# HIenthi.net
KiCad netlist of a schematic drawn in Altium Designer
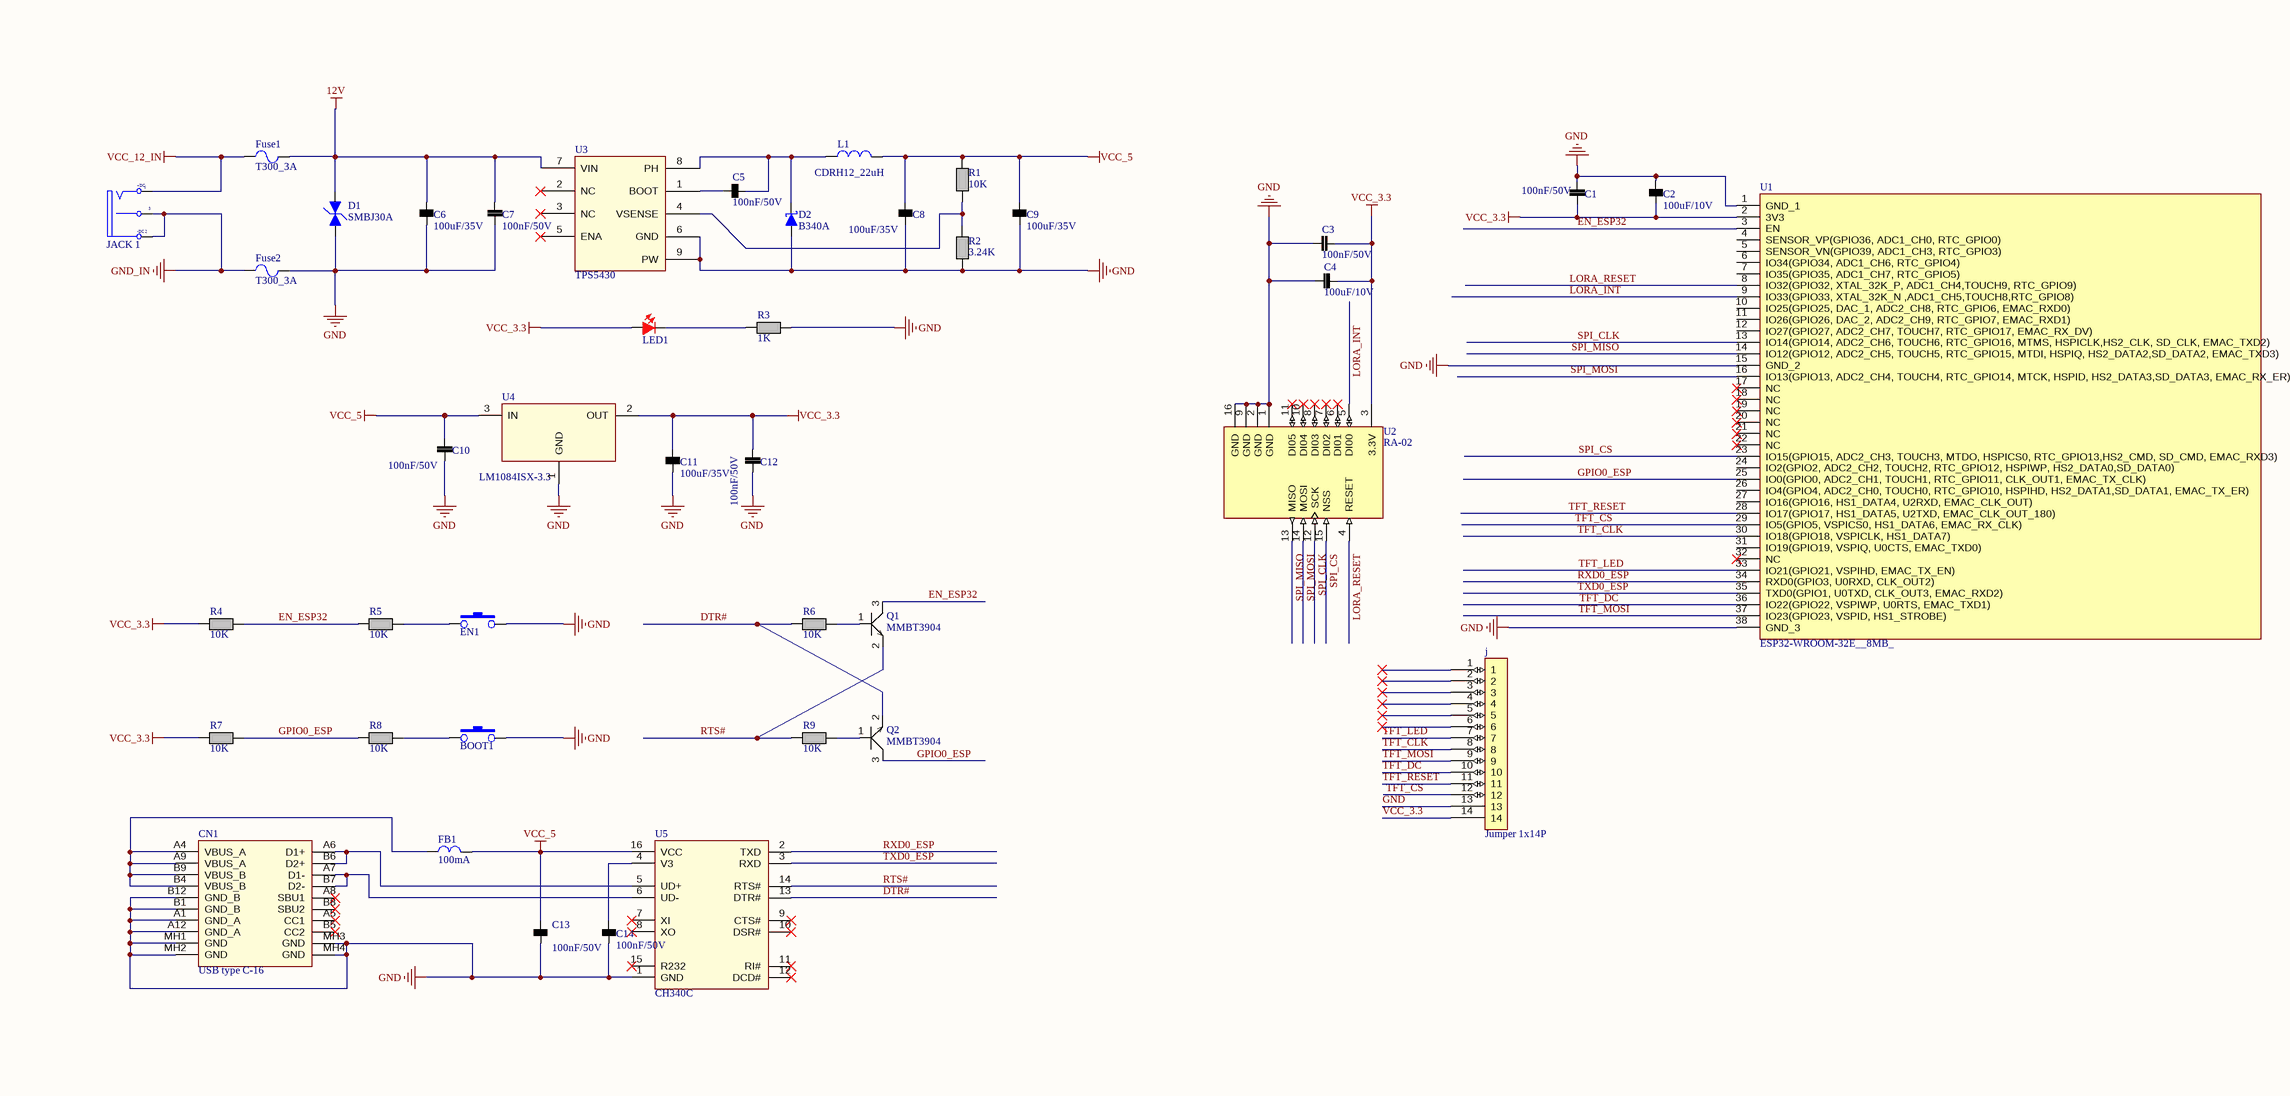
[diagram p0: HIenthi.SchDoc]

(export (version "E")
  (design (tool "Eeschema 10.0.6"))
  (components
    (comp (ref "BOOT1")
      (value "SW_2pin_SMD")
      (footprint "SW2-SMD**")
      (libsource (lib "Milky_Way") (part "SW_2pin_SMD"))
    )
    (comp (ref "C1")
      (value "100nF/50V")
      (footprint "CAP-0805**")
      (description "2Pin-SMD-0805 ,Ceramic X7R")
      (libsource (lib "Milky_Way") (part "Cap-100nF/50V_0805"))
    )
    (comp (ref "C2")
      (value "100uF/10V")
      (footprint "CAP_TANTA_SMD3528")
      (description "Cap-Tantalum  SMD3528 3.5mm x 2.8mm")
      (libsource (lib "") (part "Cap-Tanta_100uF/10V 3528_1"))
    )
    (comp (ref "C3")
      (value "100nF/50V")
      (footprint "CAP-0805**")
      (description "2Pin-SMD-0805 ,Ceramic X7R")
      (libsource (lib "Milky_Way") (part "Cap-100nF/50V_0805"))
    )
    (comp (ref "C4")
      (value "100uF/10V")
      (footprint "CAP_TANTA_SMD3528")
      (description "Cap-Tantalum  SMD3528 3.5mm x 2.8mm")
      (libsource (lib "Milky_Way") (part "Cap-Tanta_100uF/10V 3528"))
    )
    (comp (ref "C5")
      (value "100nF/50V")
      (footprint "CAP-0805**")
      (description "2Pin-SMD-0805 ,Ceramic X7R")
      (libsource (lib "Milky_Way") (part "Cap-100nF/50V_0805"))
    )
    (comp (ref "C6")
      (value "100uF/35V")
      (footprint "CAP-AL- Size D8_6.3×7.7 mm**")
      (description "Cap-Al-Size D8_6.3×7.7 mm")
      (libsource (lib "Milky_Way") (part "Cap-Al_100uF/35V"))
    )
    (comp (ref "C7")
      (value "100nF/50V")
      (footprint "CAP-0805**")
      (description "2Pin-SMD-0805 ,Ceramic X7R")
      (libsource (lib "Milky_Way") (part "Cap-100nF/50V_0805"))
    )
    (comp (ref "C8")
      (value "100uF/35V")
      (footprint "CAP-AL- Size D8_6.3×7.7 mm**")
      (description "Cap-Al-Size D8_6.3×7.7 mm")
      (libsource (lib "Milky_Way") (part "Cap-Al_100uF/35V"))
    )
    (comp (ref "C9")
      (value "100uF/35V")
      (footprint "CAP-AL- Size D8_6.3×7.7 mm**")
      (description "Cap-Al-Size D8_6.3×7.7 mm")
      (libsource (lib "Milky_Way") (part "Cap-Al_100uF/35V"))
    )
    (comp (ref "C10")
      (value "100nF/50V")
      (footprint "CAP-0805**")
      (description "2Pin-SMD-0805 ,Ceramic X7R")
      (libsource (lib "Milky_Way") (part "Cap-100nF/50V_0805"))
    )
    (comp (ref "C11")
      (value "100uF/35V")
      (footprint "CAP-AL- Size D8_6.3×7.7 mm**")
      (description "Cap-Al-Size D8_6.3×7.7 mm")
      (libsource (lib "Milky_Way") (part "Cap-Al_100uF/35V"))
    )
    (comp (ref "C12")
      (value "100nF/50V")
      (footprint "CAP-0805**")
      (description "2Pin-SMD-0805 ,Ceramic X7R")
      (libsource (lib "Milky_Way") (part "Cap-100nF/50V_0805"))
    )
    (comp (ref "C13")
      (value "100nF/50V")
      (footprint "CAP-0805**")
      (description "2Pin-SMD-0805 ,Ceramic X7R")
      (libsource (lib "Milky_Way") (part "Cap-100nF/50V_0805"))
    )
    (comp (ref "C14")
      (value "100nF/50V")
      (footprint "CAP-0805**")
      (description "2Pin-SMD-0805 ,Ceramic X7R")
      (libsource (lib "Milky_Way") (part "Cap-100nF/50V_0805"))
    )
    (comp (ref "CN1")
      (value "USB type C-16")
      (footprint "USB TYPE C-16**")
      (fields (field (name "MF") "Valcon") (field (name "MP") "CSP-USC16-TR"))
      (libsource (lib "Milky_Way") (part "USB type C-16"))
    )
    (comp (ref "D1")
      (value "SMBJ30A")
      (footprint "DO-214AA**")
      (description "DO-214AA**")
      (libsource (lib "Milky_Way") (part "D-TVS_SMBJ30A"))
    )
    (comp (ref "D2")
      (value "B340A")
      (footprint "DO-214AC**")
      (description "DO_214AC")
      (fields (field (name "PUBLISHER") "Altium Limited"))
      (libsource (lib "Milky_Way") (part "DSchottky_B340A"))
    )
    (comp (ref "EN1")
      (value "SW_2pin_SMD")
      (footprint "SW2-SMD**")
      (libsource (lib "Milky_Way") (part "SW_2pin_SMD"))
    )
    (comp (ref "FB1")
      (value "100mA")
      (footprint "FB 0805**")
      (description "FB0805/600R/0805")
      (fields (field (name "PUBLISHER") "Altium Limited"))
      (libsource (lib "Milky_Way") (part "FB0805/600R_0805"))
    )
    (comp (ref "Fuse1")
      (value "T300_3A")
      (footprint "FUSE-1812**")
      (description "SMD 1812")
      (libsource (lib "Milky_Way") (part "FUSE 3A _1812"))
    )
    (comp (ref "Fuse2")
      (value "T300_3A")
      (footprint "FUSE-1812**")
      (description "SMD 1812")
      (libsource (lib "Milky_Way") (part "FUSE 3A _1812"))
    )
    (comp (ref "j")
      (value "Jumper 1x14P")
      (footprint "IOT_v1:JUMP1x14")
      (libsource (lib "Schlib1") (part "Jumper 1x14P"))
    )
    (comp (ref "JACK 1")
      (value "DC3501")
      (footprint "DC_005**")
      (description "Jack DC3.5x1.3MM DC3501")
      (libsource (lib "IOT_v1_1") (part "Jack  DC3501"))
    )
    (comp (ref "L1")
      (value "CDRH12_22uH")
      (footprint "IND_CDRH12_12x12x7MM**")
      (description "CDRH12_12x12x7MM**")
      (fields
        (field (name "MANUFACTURER") "Generic Components")
        (field (name "PUBLISHER") "Altium Hobart Technology Centre")
      )
      (libsource (lib "Milky_Way") (part "IN_CDRH12_22uH"))
    )
    (comp (ref "LED1")
      (value "LedRed")
      (footprint "LED-0805-Red**")
      (description "2Pin-SMD")
      (libsource (lib "Milky_Way") (part "LedRed"))
    )
    (comp (ref "Q1")
      (value "MMBT3904")
      (footprint "SOT23-3 **")
      (description "3PIN-SOT23,MMBT3904")
      (libsource (lib "Milky_Way") (part "TRA-N_MMBT3904"))
    )
    (comp (ref "Q2")
      (value "MMBT3904")
      (footprint "SOT23-3 **")
      (description "3PIN-SOT23,MMBT3904")
      (libsource (lib "Milky_Way") (part "TRA-N_MMBT3904"))
    )
    (comp (ref "R1")
      (value "10K")
      (footprint "Res-0805**")
      (description "Res-10K 0805 SMD")
      (libsource (lib "Milky_Way") (part "Res-10K 0805 SMD"))
    )
    (comp (ref "R2")
      (value "3.24K")
      (footprint "Res-0805**")
      (description "Res-3.24K 0805 SMD")
      (libsource (lib "Milky_Way") (part "Res-3.24K 0805 SMD"))
    )
    (comp (ref "R3")
      (value "1K")
      (footprint "Res-0805**")
      (description "Res-1K 0805 SMD")
      (libsource (lib "Milky_Way") (part "Res-1K 0805 SMD"))
    )
    (comp (ref "R4")
      (value "10K")
      (footprint "Res-0805**")
      (description "Res-10K 0805 SMD")
      (libsource (lib "Milky_Way") (part "Res-10K 0805 SMD"))
    )
    (comp (ref "R5")
      (value "10K")
      (footprint "Res-0805**")
      (description "Res-10K 0805 SMD")
      (libsource (lib "Milky_Way") (part "Res-10K 0805 SMD"))
    )
    (comp (ref "R6")
      (value "10K")
      (footprint "Res-0805**")
      (description "Res-10K 0805 SMD")
      (libsource (lib "Milky_Way") (part "Res-10K 0805 SMD"))
    )
    (comp (ref "R7")
      (value "10K")
      (footprint "Res-0805**")
      (description "Res-10K 0805 SMD")
      (libsource (lib "Milky_Way") (part "Res-10K 0805 SMD"))
    )
    (comp (ref "R8")
      (value "10K")
      (footprint "Res-0805**")
      (description "Res-10K 0805 SMD")
      (libsource (lib "Milky_Way") (part "Res-10K 0805 SMD"))
    )
    (comp (ref "R9")
      (value "10K")
      (footprint "Res-0805**")
      (description "Res-10K 0805 SMD")
      (libsource (lib "Milky_Way") (part "Res-10K 0805 SMD"))
    )
    (comp (ref "U1")
      (value "ESP32-WROOM-32E__8MB_")
      (footprint "ESP32WROOM32E8MB")
      (description "Integrated Circuit")
      (fields
        (field (name "MANUFACTURER_PART_NUMBER") "ESP32-WROOM-32E (8MB)")
        (field (name "MOUSER PART NUMBER") "356-ESP32WRM32E164PH")
      )
      (libsource (lib "IOT_v1_1") (part "ESP32-WROOM-32E__8MB_"))
    )
    (comp (ref "U2")
      (value "RA-02")
      (footprint "RA-02")
      (fields (field (name "MF") "Ai-Thinker"))
      (libsource (lib "RA-02") (part "RA-02"))
    )
    (comp (ref "U3")
      (value "TPS5430")
      (footprint "SOIC8-PAD**")
      (description "SOIC8 pad-Height 1.7mm")
      (libsource (lib "Milky_Way") (part "TPS5430"))
    )
    (comp (ref "U4")
      (value "LM1084ISX-3.3")
      (footprint "TO-263/D2PAK")
      (description "TO263-3")
      (libsource (lib "Milky_Way") (part "LM1084ISX-3.3"))
    )
    (comp (ref "U5")
      (value "CH340C")
      (footprint "SOIC-16**")
      (description "16Pin-SOIC")
      (libsource (lib "Milky_Way") (part "CH340C"))
    )
  )
  (nets
    (net (code "1") (name "/DTR#") (class "Default")
      (node (ref "Q2") (pin "2") (pinfunction "2_2") (pintype "passive"))
      (node (ref "R6") (pin "2") (pinfunction "2_2") (pintype "passive"))
      (node (ref "U5") (pin "13") (pinfunction "DTR#_13") (pintype "passive"))
    )
    (net (code "2") (name "/EN_ESP32") (class "Default")
      (node (ref "Q1") (pin "3") (pinfunction "3_3") (pintype "passive"))
      (node (ref "R4") (pin "1") (pinfunction "1_1") (pintype "passive"))
      (node (ref "R5") (pin "2") (pinfunction "2_2") (pintype "passive"))
      (node (ref "U1") (pin "3") (pinfunction "EN_3") (pintype "passive"))
    )
    (net (code "3") (name "/GPIO0_ESP") (class "Default")
      (node (ref "Q2") (pin "3") (pinfunction "3_3") (pintype "passive"))
      (node (ref "R7") (pin "1") (pinfunction "1_1") (pintype "passive"))
      (node (ref "R8") (pin "2") (pinfunction "2_2") (pintype "passive"))
      (node (ref "U1") (pin "25") (pinfunction "IO0(GPIO0,_ADC2_CH1,_TOUCH1,_RTC_GPIO11,_CLK_OUT1,_EMAC_TX_CLK)_25") (pintype "passive"))
    )
    (net (code "4") (name "/LORA_INT") (class "Default")
      (node (ref "U1") (pin "9") (pinfunction "IO33(GPIO33,_XTAL_32K_N_,ADC1_CH5,TOUCH8,RTC_GPIO8)_9") (pintype "passive"))
      (node (ref "U2") (pin "5") (pinfunction "DI00_5") (pintype "bidirectional"))
    )
    (net (code "5") (name "/LORA_RESET") (class "Default")
      (node (ref "U1") (pin "8") (pinfunction "IO32(GPIO32,_XTAL_32K_P,_ADC1_CH4,TOUCH9,_RTC_GPIO9)_8") (pintype "passive"))
      (node (ref "U2") (pin "4") (pinfunction "RESET_4") (pintype "input"))
    )
    (net (code "6") (name "/RTS#") (class "Default")
      (node (ref "Q1") (pin "2") (pinfunction "2_2") (pintype "passive"))
      (node (ref "R9") (pin "2") (pinfunction "2_2") (pintype "passive"))
      (node (ref "U5") (pin "14") (pinfunction "RTS#_14") (pintype "passive"))
    )
    (net (code "7") (name "/RXD0_ESP") (class "Default")
      (node (ref "U1") (pin "34") (pinfunction "RXD0(GPIO3,_U0RXD,_CLK_OUT2)_34") (pintype "passive"))
      (node (ref "U5") (pin "2") (pinfunction "TXD_2") (pintype "passive"))
    )
    (net (code "8") (name "/SPI_CLK") (class "Default")
      (node (ref "U1") (pin "13") (pinfunction "IO14(GPIO14,_ADC2_CH6,_TOUCH6,_RTC_GPIO16,_MTMS,_HSPICLK,HS2_CLK,_SD_CLK,_EMAC_TXD2)_13") (pintype "passive"))
      (node (ref "U2") (pin "12") (pinfunction "SCK_12") (pintype "input"))
    )
    (net (code "9") (name "/SPI_CS") (class "Default")
      (node (ref "U1") (pin "23") (pinfunction "IO15(GPIO15,_ADC2_CH3,_TOUCH3,_MTDO,_HSPICS0,_RTC_GPIO13,HS2_CMD,_SD_CMD,_EMAC_RXD3)_23") (pintype "passive"))
      (node (ref "U2") (pin "15") (pinfunction "NSS_15") (pintype "input"))
    )
    (net (code "10") (name "/SPI_MISO") (class "Default")
      (node (ref "U1") (pin "14") (pinfunction "IO12(GPIO12,_ADC2_CH5,_TOUCH5,_RTC_GPIO15,_MTDI,_HSPIQ,_HS2_DATA2,SD_DATA2,_EMAC_TXD3)_14") (pintype "passive"))
      (node (ref "U2") (pin "13") (pinfunction "MISO_13") (pintype "output"))
    )
    (net (code "11") (name "/SPI_MOSI") (class "Default")
      (node (ref "U1") (pin "16") (pinfunction "IO13(GPIO13,_ADC2_CH4,_TOUCH4,_RTC_GPIO14,_MTCK,_HSPID,_HS2_DATA3,SD_DATA3,_EMAC_RX_ER)_16") (pintype "passive"))
      (node (ref "U2") (pin "14") (pinfunction "MOSI_14") (pintype "input"))
    )
    (net (code "12") (name "/TFT_CLK") (class "Default")
      (node (ref "U1") (pin "30") (pinfunction "IO18(GPIO18,_VSPICLK,_HS1_DATA7)_30") (pintype "passive"))
      (node (ref "j") (pin "8") (pinfunction "8_8") (pintype "bidirectional"))
    )
    (net (code "13") (name "/TFT_CS") (class "Default")
      (node (ref "U1") (pin "29") (pinfunction "IO5(GPIO5,_VSPICS0,_HS1_DATA6,_EMAC_RX_CLK)_29") (pintype "passive"))
      (node (ref "j") (pin "12") (pinfunction "12_12") (pintype "bidirectional"))
    )
    (net (code "14") (name "/TFT_DC") (class "Default")
      (node (ref "U1") (pin "36") (pinfunction "IO22(GPIO22,_VSPIWP,_U0RTS,_EMAC_TXD1)_36") (pintype "passive"))
      (node (ref "j") (pin "10") (pinfunction "10_10") (pintype "bidirectional"))
    )
    (net (code "15") (name "/TFT_LED") (class "Default")
      (node (ref "U1") (pin "33") (pinfunction "IO21(GPIO21,_VSPIHD,_EMAC_TX_EN)_33") (pintype "passive"))
      (node (ref "j") (pin "7") (pinfunction "7_7") (pintype "bidirectional"))
    )
    (net (code "16") (name "/TFT_MOSI") (class "Default")
      (node (ref "U1") (pin "37") (pinfunction "IO23(GPIO23,_VSPID,_HS1_STROBE)_37") (pintype "passive"))
      (node (ref "j") (pin "9") (pinfunction "9_9") (pintype "bidirectional"))
    )
    (net (code "17") (name "/TFT_RESET") (class "Default")
      (node (ref "U1") (pin "28") (pinfunction "IO17(GPIO17,_HS1_DATA5,_U2TXD,_EMAC_CLK_OUT_180)_28") (pintype "passive"))
      (node (ref "j") (pin "11") (pinfunction "11_11") (pintype "bidirectional"))
    )
    (net (code "18") (name "/TXD0_ESP") (class "Default")
      (node (ref "U1") (pin "35") (pinfunction "TXD0(GPIO1,_U0TXD,_CLK_OUT3,_EMAC_RXD2)_35") (pintype "passive"))
      (node (ref "U5") (pin "3") (pinfunction "RXD_3") (pintype "passive"))
    )
    (net (code "19") (name "12V") (class "Default")
      (node (ref "C6") (pin "1") (pinfunction "+_1") (pintype "passive"))
      (node (ref "C7") (pin "2") (pinfunction "2_2") (pintype "passive"))
      (node (ref "D1") (pin "2") (pinfunction "A_2") (pintype "passive"))
      (node (ref "Fuse1") (pin "2") (pinfunction "2_2") (pintype "passive"))
      (node (ref "U3") (pin "7") (pinfunction "VIN_7") (pintype "passive"))
    )
    (net (code "20") (name "GND") (class "Default")
      (node (ref "BOOT1") (pin "2") (pinfunction "2_2") (pintype "passive"))
      (node (ref "C1") (pin "2") (pinfunction "2_2") (pintype "passive"))
      (node (ref "C10") (pin "1") (pinfunction "1_1") (pintype "passive"))
      (node (ref "C11") (pin "2") (pinfunction "-_2") (pintype "passive"))
      (node (ref "C12") (pin "1") (pinfunction "1_1") (pintype "passive"))
      (node (ref "C13") (pin "2") (pinfunction "2_2") (pintype "passive"))
      (node (ref "C14") (pin "2") (pinfunction "2_2") (pintype "passive"))
      (node (ref "C2") (pin "2") (pinfunction "-_2") (pintype "passive"))
      (node (ref "C3") (pin "1") (pinfunction "1_1") (pintype "passive"))
      (node (ref "C4") (pin "2") (pinfunction "-_2") (pintype "passive"))
      (node (ref "C6") (pin "2") (pinfunction "-_2") (pintype "passive"))
      (node (ref "C7") (pin "1") (pinfunction "1_1") (pintype "passive"))
      (node (ref "C8") (pin "2") (pinfunction "-_2") (pintype "passive"))
      (node (ref "C9") (pin "2") (pinfunction "-_2") (pintype "passive"))
      (node (ref "CN1") (pin "A1") (pinfunction "GND_A_A1") (pintype "power_in"))
      (node (ref "CN1") (pin "A12") (pinfunction "GND_A_A12") (pintype "power_in"))
      (node (ref "CN1") (pin "B1") (pinfunction "GND_B_B1") (pintype "power_in"))
      (node (ref "CN1") (pin "B12") (pinfunction "GND_B_B12") (pintype "power_in"))
      (node (ref "CN1") (pin "MH1") (pinfunction "GND_MH1") (pintype "power_in"))
      (node (ref "CN1") (pin "MH2") (pinfunction "GND_MH2") (pintype "power_in"))
      (node (ref "CN1") (pin "MH3") (pinfunction "GND_MH3") (pintype "power_in"))
      (node (ref "CN1") (pin "MH4") (pinfunction "GND_MH4") (pintype "power_in"))
      (node (ref "D1") (pin "1") (pinfunction "A_1") (pintype "passive"))
      (node (ref "D2") (pin "1") (pinfunction "A_1") (pintype "passive"))
      (node (ref "EN1") (pin "2") (pinfunction "2_2") (pintype "passive"))
      (node (ref "Fuse2") (pin "2") (pinfunction "2_2") (pintype "passive"))
      (node (ref "R2") (pin "1") (pinfunction "1_1") (pintype "passive"))
      (node (ref "R3") (pin "1") (pinfunction "1_1") (pintype "passive"))
      (node (ref "U1") (pin "1") (pinfunction "GND_1_1") (pintype "passive"))
      (node (ref "U1") (pin "15") (pinfunction "GND_2_15") (pintype "passive"))
      (node (ref "U1") (pin "38") (pinfunction "GND_3_38") (pintype "passive"))
      (node (ref "U2") (pin "1") (pinfunction "GND_1") (pintype "power_in"))
      (node (ref "U2") (pin "16") (pinfunction "GND_16") (pintype "power_in"))
      (node (ref "U2") (pin "2") (pinfunction "GND_2") (pintype "power_in"))
      (node (ref "U2") (pin "9") (pinfunction "GND_9") (pintype "power_in"))
      (node (ref "U3") (pin "6") (pinfunction "GND_6") (pintype "passive"))
      (node (ref "U3") (pin "9") (pinfunction "PW_9") (pintype "passive"))
      (node (ref "U4") (pin "1") (pinfunction "GND_1") (pintype "passive"))
      (node (ref "U5") (pin "1") (pinfunction "GND_1") (pintype "passive"))
      (node (ref "j") (pin "13") (pinfunction "13_13") (pintype "power_in"))
    )
    (net (code "21") (name "GND_IN") (class "Default")
      (node (ref "Fuse2") (pin "1") (pinfunction "1_1") (pintype "passive"))
      (node (ref "JACK 1") (pin "2") (pinfunction "TN_2") (pintype "passive"))
      (node (ref "JACK 1") (pin "3") (pinfunction "S_3") (pintype "power_in"))
    )
    (net (code "22") (name "Net-(BOOT1-Pad1)") (class "Default")
      (node (ref "BOOT1") (pin "1") (pinfunction "1_1") (pintype "passive"))
      (node (ref "R8") (pin "1") (pinfunction "1_1") (pintype "passive"))
    )
    (net (code "23") (name "Net-(CN1-D1+)") (class "Default")
      (node (ref "CN1") (pin "A6") (pinfunction "D1+_A6") (pintype "passive"))
      (node (ref "CN1") (pin "B6") (pinfunction "D2+_B6") (pintype "passive"))
      (node (ref "U5") (pin "5") (pinfunction "UD+_5") (pintype "passive"))
    )
    (net (code "24") (name "Net-(CN1-D1-)") (class "Default")
      (node (ref "CN1") (pin "A7") (pinfunction "D1-_A7") (pintype "passive"))
      (node (ref "CN1") (pin "B7") (pinfunction "D2-_B7") (pintype "passive"))
      (node (ref "U5") (pin "6") (pinfunction "UD-_6") (pintype "passive"))
    )
    (net (code "25") (name "Net-(CN1-VBUS_A-PadA4)") (class "Default")
      (node (ref "CN1") (pin "A4") (pinfunction "VBUS_A_A4") (pintype "power_in"))
      (node (ref "CN1") (pin "A9") (pinfunction "VBUS_A_A9") (pintype "power_in"))
      (node (ref "CN1") (pin "B4") (pinfunction "VBUS_B_B4") (pintype "power_in"))
      (node (ref "CN1") (pin "B9") (pinfunction "VBUS_B_B9") (pintype "power_in"))
      (node (ref "FB1") (pin "1") (pinfunction "1_1") (pintype "passive"))
    )
    (net (code "26") (name "Net-(D2-K)") (class "Default")
      (node (ref "C5") (pin "2") (pinfunction "2_2") (pintype "passive"))
      (node (ref "D2") (pin "2") (pinfunction "K_2") (pintype "passive"))
      (node (ref "L1") (pin "1") (pinfunction "1_1") (pintype "passive"))
      (node (ref "U3") (pin "8") (pinfunction "PH_8") (pintype "passive"))
    )
    (net (code "27") (name "Net-(EN1-Pad1)") (class "Default")
      (node (ref "EN1") (pin "1") (pinfunction "1_1") (pintype "passive"))
      (node (ref "R5") (pin "1") (pinfunction "1_1") (pintype "passive"))
    )
    (net (code "28") (name "Net-(LED1-K)") (class "Default")
      (node (ref "LED1") (pin "2") (pinfunction "K_2") (pintype "passive"))
      (node (ref "R3") (pin "2") (pinfunction "2_2") (pintype "passive"))
    )
    (net (code "29") (name "Net-(Q1-Pad1)") (class "Default")
      (node (ref "Q1") (pin "1") (pinfunction "1_1") (pintype "passive"))
      (node (ref "R6") (pin "1") (pinfunction "1_1") (pintype "passive"))
    )
    (net (code "30") (name "Net-(Q2-Pad1)") (class "Default")
      (node (ref "Q2") (pin "1") (pinfunction "1_1") (pintype "passive"))
      (node (ref "R9") (pin "1") (pinfunction "1_1") (pintype "passive"))
    )
    (net (code "31") (name "Net-(U3-BOOT)") (class "Default")
      (node (ref "C5") (pin "1") (pinfunction "1_1") (pintype "passive"))
      (node (ref "U3") (pin "1") (pinfunction "BOOT_1") (pintype "passive"))
    )
    (net (code "32") (name "Net-(U3-VSENSE)") (class "Default")
      (node (ref "R1") (pin "1") (pinfunction "1_1") (pintype "passive"))
      (node (ref "R2") (pin "2") (pinfunction "2_2") (pintype "passive"))
      (node (ref "U3") (pin "4") (pinfunction "VSENSE_4") (pintype "passive"))
    )
    (net (code "33") (name "Net-(U5-V3)") (class "Default")
      (node (ref "C14") (pin "1") (pinfunction "1_1") (pintype "passive"))
      (node (ref "U5") (pin "4") (pinfunction "V3_4") (pintype "passive"))
    )
    (net (code "34") (name "VCC_3.3") (class "Default")
      (node (ref "C1") (pin "1") (pinfunction "1_1") (pintype "passive"))
      (node (ref "C11") (pin "1") (pinfunction "+_1") (pintype "passive"))
      (node (ref "C12") (pin "2") (pinfunction "2_2") (pintype "passive"))
      (node (ref "C2") (pin "1") (pinfunction "+_1") (pintype "passive"))
      (node (ref "C3") (pin "2") (pinfunction "2_2") (pintype "passive"))
      (node (ref "C4") (pin "1") (pinfunction "+_1") (pintype "passive"))
      (node (ref "LED1") (pin "1") (pinfunction "A_1") (pintype "passive"))
      (node (ref "R4") (pin "2") (pinfunction "2_2") (pintype "passive"))
      (node (ref "R7") (pin "2") (pinfunction "2_2") (pintype "passive"))
      (node (ref "U1") (pin "2") (pinfunction "3V3_2") (pintype "passive"))
      (node (ref "U2") (pin "3") (pinfunction "3.3V_3") (pintype "power_in"))
      (node (ref "U4") (pin "2") (pinfunction "OUT_2") (pintype "passive"))
      (node (ref "j") (pin "14") (pinfunction "14_14") (pintype "power_in"))
    )
    (net (code "35") (name "VCC_5") (class "Default")
      (node (ref "C10") (pin "2") (pinfunction "2_2") (pintype "passive"))
      (node (ref "C13") (pin "1") (pinfunction "1_1") (pintype "passive"))
      (node (ref "C8") (pin "1") (pinfunction "+_1") (pintype "passive"))
      (node (ref "C9") (pin "1") (pinfunction "+_1") (pintype "passive"))
      (node (ref "FB1") (pin "2") (pinfunction "2_2") (pintype "passive"))
      (node (ref "L1") (pin "2") (pinfunction "2_2") (pintype "passive"))
      (node (ref "R1") (pin "2") (pinfunction "2_2") (pintype "passive"))
      (node (ref "U4") (pin "3") (pinfunction "IN_3") (pintype "passive"))
      (node (ref "U5") (pin "16") (pinfunction "VCC_16") (pintype "passive"))
    )
    (net (code "36") (name "VCC_12_IN") (class "Default")
      (node (ref "Fuse1") (pin "1") (pinfunction "1_1") (pintype "passive"))
      (node (ref "JACK 1") (pin "1") (pinfunction "T_1") (pintype "passive"))
    )
    (net (code "37") (name "unconnected-(CN1-CC1-PadA5)") (class "Default")
      (node (ref "CN1") (pin "A5") (pinfunction "CC1_A5") (pintype "passive+no_connect"))
    )
    (net (code "38") (name "unconnected-(CN1-CC2-PadB5)") (class "Default")
      (node (ref "CN1") (pin "B5") (pinfunction "CC2_B5") (pintype "passive+no_connect"))
    )
    (net (code "39") (name "unconnected-(CN1-SBU1-PadA8)") (class "Default")
      (node (ref "CN1") (pin "A8") (pinfunction "SBU1_A8") (pintype "passive+no_connect"))
    )
    (net (code "40") (name "unconnected-(CN1-SBU2-PadB8)") (class "Default")
      (node (ref "CN1") (pin "B8") (pinfunction "SBU2_B8") (pintype "passive+no_connect"))
    )
    (net (code "41") (name "unconnected-(U1-IO2(GPIO2,_ADC2_CH2,_TOUCH2,_RTC_GPIO12,_HSPIWP,_HS2_DATA0,SD_DATA0)-Pad24)") (class "Default")
      (node (ref "U1") (pin "24") (pinfunction "IO2(GPIO2,_ADC2_CH2,_TOUCH2,_RTC_GPIO12,_HSPIWP,_HS2_DATA0,SD_DATA0)_24") (pintype "passive"))
    )
    (net (code "42") (name "unconnected-(U1-IO4(GPIO4,_ADC2_CH0,_TOUCH0,_RTC_GPIO10,_HSPIHD,_HS2_DATA1,SD_DATA1,_EMAC_TX_ER)-Pad26)") (class "Default")
      (node (ref "U1") (pin "26") (pinfunction "IO4(GPIO4,_ADC2_CH0,_TOUCH0,_RTC_GPIO10,_HSPIHD,_HS2_DATA1,SD_DATA1,_EMAC_TX_ER)_26") (pintype "passive"))
    )
    (net (code "43") (name "unconnected-(U1-IO16(GPIO16,_HS1_DATA4,_U2RXD,_EMAC_CLK_OUT)-Pad27)") (class "Default")
      (node (ref "U1") (pin "27") (pinfunction "IO16(GPIO16,_HS1_DATA4,_U2RXD,_EMAC_CLK_OUT)_27") (pintype "passive"))
    )
    (net (code "44") (name "unconnected-(U1-IO19(GPIO19,_VSPIQ,_U0CTS,_EMAC_TXD0)-Pad31)") (class "Default")
      (node (ref "U1") (pin "31") (pinfunction "IO19(GPIO19,_VSPIQ,_U0CTS,_EMAC_TXD0)_31") (pintype "passive"))
    )
    (net (code "45") (name "unconnected-(U1-IO25(GPIO25,_DAC_1,_ADC2_CH8,_RTC_GPIO6,_EMAC_RXD0)-Pad10)") (class "Default")
      (node (ref "U1") (pin "10") (pinfunction "IO25(GPIO25,_DAC_1,_ADC2_CH8,_RTC_GPIO6,_EMAC_RXD0)_10") (pintype "passive"))
    )
    (net (code "46") (name "unconnected-(U1-IO26(GPIO26,_DAC_2,_ADC2_CH9,_RTC_GPIO7,_EMAC_RXD1)-Pad11)") (class "Default")
      (node (ref "U1") (pin "11") (pinfunction "IO26(GPIO26,_DAC_2,_ADC2_CH9,_RTC_GPIO7,_EMAC_RXD1)_11") (pintype "passive"))
    )
    (net (code "47") (name "unconnected-(U1-IO27(GPIO27,_ADC2_CH7,_TOUCH7,_RTC_GPIO17,_EMAC_RX_DV)-Pad12)") (class "Default")
      (node (ref "U1") (pin "12") (pinfunction "IO27(GPIO27,_ADC2_CH7,_TOUCH7,_RTC_GPIO17,_EMAC_RX_DV)_12") (pintype "passive"))
    )
    (net (code "48") (name "unconnected-(U1-IO34(GPIO34,_ADC1_CH6,_RTC_GPIO4)-Pad6)") (class "Default")
      (node (ref "U1") (pin "6") (pinfunction "IO34(GPIO34,_ADC1_CH6,_RTC_GPIO4)_6") (pintype "passive"))
    )
    (net (code "49") (name "unconnected-(U1-IO35(GPIO35,_ADC1_CH7,_RTC_GPIO5)-Pad7)") (class "Default")
      (node (ref "U1") (pin "7") (pinfunction "IO35(GPIO35,_ADC1_CH7,_RTC_GPIO5)_7") (pintype "passive"))
    )
    (net (code "50") (name "unconnected-(U1-NC-Pad17)") (class "Default")
      (node (ref "U1") (pin "17") (pinfunction "NC_17") (pintype "passive+no_connect"))
    )
    (net (code "51") (name "unconnected-(U1-NC-Pad18)") (class "Default")
      (node (ref "U1") (pin "18") (pinfunction "NC_18") (pintype "passive+no_connect"))
    )
    (net (code "52") (name "unconnected-(U1-NC-Pad19)") (class "Default")
      (node (ref "U1") (pin "19") (pinfunction "NC_19") (pintype "passive+no_connect"))
    )
    (net (code "53") (name "unconnected-(U1-NC-Pad20)") (class "Default")
      (node (ref "U1") (pin "20") (pinfunction "NC_20") (pintype "passive+no_connect"))
    )
    (net (code "54") (name "unconnected-(U1-NC-Pad21)") (class "Default")
      (node (ref "U1") (pin "21") (pinfunction "NC_21") (pintype "passive+no_connect"))
    )
    (net (code "55") (name "unconnected-(U1-NC-Pad22)") (class "Default")
      (node (ref "U1") (pin "22") (pinfunction "NC_22") (pintype "passive+no_connect"))
    )
    (net (code "56") (name "unconnected-(U1-NC-Pad32)") (class "Default")
      (node (ref "U1") (pin "32") (pinfunction "NC_32") (pintype "passive+no_connect"))
    )
    (net (code "57") (name "unconnected-(U1-SENSOR_VN(GPIO39,_ADC1_CH3,_RTC_GPIO3)-Pad5)") (class "Default")
      (node (ref "U1") (pin "5") (pinfunction "SENSOR_VN(GPIO39,_ADC1_CH3,_RTC_GPIO3)_5") (pintype "passive"))
    )
    (net (code "58") (name "unconnected-(U1-SENSOR_VP(GPIO36,_ADC1_CH0,_RTC_GPIO0)-Pad4)") (class "Default")
      (node (ref "U1") (pin "4") (pinfunction "SENSOR_VP(GPIO36,_ADC1_CH0,_RTC_GPIO0)_4") (pintype "passive"))
    )
    (net (code "59") (name "unconnected-(U2-DI01-Pad6)") (class "Default")
      (node (ref "U2") (pin "6") (pinfunction "DI01_6") (pintype "bidirectional+no_connect"))
    )
    (net (code "60") (name "unconnected-(U2-DI02-Pad7)") (class "Default")
      (node (ref "U2") (pin "7") (pinfunction "DI02_7") (pintype "bidirectional+no_connect"))
    )
    (net (code "61") (name "unconnected-(U2-DI03-Pad8)") (class "Default")
      (node (ref "U2") (pin "8") (pinfunction "DI03_8") (pintype "bidirectional+no_connect"))
    )
    (net (code "62") (name "unconnected-(U2-DI04-Pad10)") (class "Default")
      (node (ref "U2") (pin "10") (pinfunction "DI04_10") (pintype "bidirectional+no_connect"))
    )
    (net (code "63") (name "unconnected-(U2-DI05-Pad11)") (class "Default")
      (node (ref "U2") (pin "11") (pinfunction "DI05_11") (pintype "bidirectional+no_connect"))
    )
    (net (code "64") (name "unconnected-(U3-ENA-Pad5)") (class "Default")
      (node (ref "U3") (pin "5") (pinfunction "ENA_5") (pintype "passive+no_connect"))
    )
    (net (code "65") (name "unconnected-(U3-NC-Pad2)") (class "Default")
      (node (ref "U3") (pin "2") (pinfunction "NC_2") (pintype "passive+no_connect"))
    )
    (net (code "66") (name "unconnected-(U3-NC-Pad3)") (class "Default")
      (node (ref "U3") (pin "3") (pinfunction "NC_3") (pintype "passive+no_connect"))
    )
    (net (code "67") (name "unconnected-(U5-CTS#-Pad9)") (class "Default")
      (node (ref "U5") (pin "9") (pinfunction "CTS#_9") (pintype "passive+no_connect"))
    )
    (net (code "68") (name "unconnected-(U5-DCD#-Pad12)") (class "Default")
      (node (ref "U5") (pin "12") (pinfunction "DCD#_12") (pintype "passive+no_connect"))
    )
    (net (code "69") (name "unconnected-(U5-DSR#-Pad10)") (class "Default")
      (node (ref "U5") (pin "10") (pinfunction "DSR#_10") (pintype "passive+no_connect"))
    )
    (net (code "70") (name "unconnected-(U5-R232-Pad15)") (class "Default")
      (node (ref "U5") (pin "15") (pinfunction "R232_15") (pintype "passive+no_connect"))
    )
    (net (code "71") (name "unconnected-(U5-RI#-Pad11)") (class "Default")
      (node (ref "U5") (pin "11") (pinfunction "RI#_11") (pintype "passive+no_connect"))
    )
    (net (code "72") (name "unconnected-(U5-XI-Pad7)") (class "Default")
      (node (ref "U5") (pin "7") (pinfunction "XI_7") (pintype "passive+no_connect"))
    )
    (net (code "73") (name "unconnected-(U5-XO-Pad8)") (class "Default")
      (node (ref "U5") (pin "8") (pinfunction "XO_8") (pintype "passive+no_connect"))
    )
    (net (code "74") (name "unconnected-(j-Pad1)") (class "Default")
      (node (ref "j") (pin "1") (pinfunction "1_1") (pintype "bidirectional+no_connect"))
    )
    (net (code "75") (name "unconnected-(j-Pad2)") (class "Default")
      (node (ref "j") (pin "2") (pinfunction "2_2") (pintype "bidirectional+no_connect"))
    )
    (net (code "76") (name "unconnected-(j-Pad3)") (class "Default")
      (node (ref "j") (pin "3") (pinfunction "3_3") (pintype "bidirectional+no_connect"))
    )
    (net (code "77") (name "unconnected-(j-Pad4)") (class "Default")
      (node (ref "j") (pin "4") (pinfunction "4_4") (pintype "bidirectional+no_connect"))
    )
    (net (code "78") (name "unconnected-(j-Pad5)") (class "Default")
      (node (ref "j") (pin "5") (pinfunction "5_5") (pintype "bidirectional+no_connect"))
    )
    (net (code "79") (name "unconnected-(j-Pad6)") (class "Default")
      (node (ref "j") (pin "6") (pinfunction "6_6") (pintype "bidirectional+no_connect"))
    )
  )
)
